# Heater.net
KiCad netlist of a schematic drawn in Altium Designer
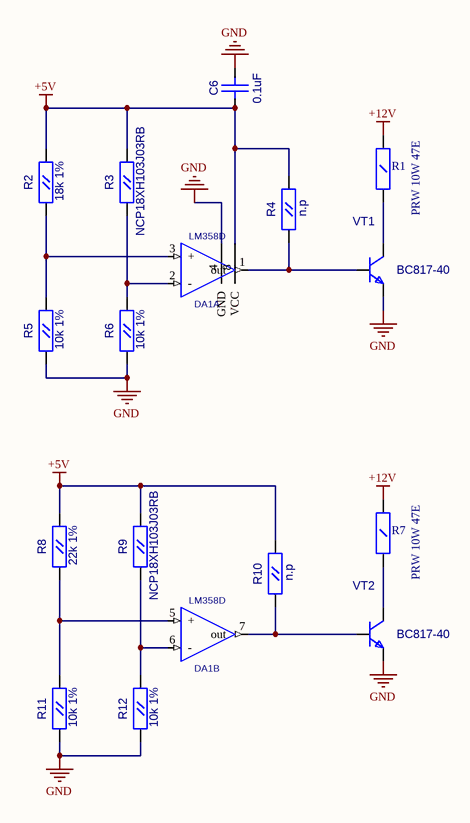
[diagram p0: Heater.SchDoc]

(export (version "E")
  (design (tool "Eeschema 10.0.6"))
  (components
    (comp (ref "C6")
      (value "0.1uF")
      (footprint "CC0603")
      (description "CC0603")
      (libsource (lib "gprs_modem_2") (part "CC0603"))
    )
    (comp (ref "DA1") (value "LM358D") (footprint "SO-8") (libsource (lib "Schetchik") (part "LM358D")))
    (comp (ref "R1")
      (value "PRW 10W 47E")
      (footprint "R_5W_Cement")
      (libsource (lib "gprs_modem_2") (part "R_10W"))
    )
    (comp (ref "R2")
      (value "18k 1%")
      (footprint "RC0603")
      (description "RC0603")
      (libsource (lib "gprs_modem_2") (part "RC0603"))
    )
    (comp (ref "R3")
      (value "NCP18XH103J03RB")
      (footprint "RC0603")
      (description "RC0603")
      (libsource (lib "gprs_modem_2") (part "RC0603"))
    )
    (comp (ref "R4")
      (value "n.p")
      (footprint "RC0603")
      (description "RC0603")
      (libsource (lib "gprs_modem_2") (part "RC0603"))
    )
    (comp (ref "R5")
      (value "10k 1%")
      (footprint "RC0603")
      (description "RC0603")
      (libsource (lib "gprs_modem_2") (part "RC0603"))
    )
    (comp (ref "R6")
      (value "10k 1%")
      (footprint "RC0603")
      (description "RC0603")
      (libsource (lib "gprs_modem_2") (part "RC0603"))
    )
    (comp (ref "R7")
      (value "PRW 10W 47E")
      (footprint "R_5W_Cement")
      (libsource (lib "gprs_modem_2") (part "R_10W"))
    )
    (comp (ref "R8")
      (value "22k 1%")
      (footprint "RC0603")
      (description "RC0603")
      (libsource (lib "gprs_modem_2") (part "RC0603"))
    )
    (comp (ref "R9")
      (value "NCP18XH103J03RB")
      (footprint "RC0603")
      (description "RC0603")
      (libsource (lib "gprs_modem_2") (part "RC0603"))
    )
    (comp (ref "R10")
      (value "n.p")
      (footprint "RC0603")
      (description "RC0603")
      (libsource (lib "gprs_modem_2") (part "RC0603"))
    )
    (comp (ref "R11")
      (value "10k 1%")
      (footprint "RC0603")
      (description "RC0603")
      (libsource (lib "gprs_modem_2") (part "RC0603"))
    )
    (comp (ref "R12")
      (value "10k 1%")
      (footprint "RC0603")
      (description "RC0603")
      (libsource (lib "gprs_modem_2") (part "RC0603"))
    )
    (comp (ref "VT1")
      (value "BC817-40")
      (footprint "SOT-23(123)")
      (description "NPN 500ma transistor")
      (libsource (lib "gprs_modem_2") (part "BC846BLT1"))
    )
    (comp (ref "VT2")
      (value "BC817-40")
      (footprint "SOT-23(123)")
      (description "NPN 500ma transistor")
      (libsource (lib "gprs_modem_2") (part "BC846BLT1"))
    )
  )
  (nets
    (net (code "1") (name "+5V") (class "Default")
      (node (ref "C6") (pin "1") (pinfunction "A_1") (pintype "passive"))
      (node (ref "DA1") (pin "8") (pinfunction "VCC_8") (pintype "power_in"))
      (node (ref "R10") (pin "2") (pinfunction "B_2") (pintype "passive"))
      (node (ref "R2") (pin "2") (pinfunction "B_2") (pintype "passive"))
      (node (ref "R3") (pin "2") (pinfunction "B_2") (pintype "passive"))
      (node (ref "R4") (pin "2") (pinfunction "B_2") (pintype "passive"))
      (node (ref "R8") (pin "2") (pinfunction "B_2") (pintype "passive"))
      (node (ref "R9") (pin "2") (pinfunction "B_2") (pintype "passive"))
    )
    (net (code "2") (name "+12V") (class "Default")
      (node (ref "R1") (pin "2") (pinfunction "B_2") (pintype "passive"))
      (node (ref "R7") (pin "2") (pinfunction "B_2") (pintype "passive"))
    )
    (net (code "3") (name "GND") (class "Default")
      (node (ref "C6") (pin "2") (pinfunction "B_2") (pintype "passive"))
      (node (ref "DA1") (pin "4") (pinfunction "GND_4") (pintype "power_in"))
      (node (ref "R11") (pin "1") (pinfunction "A_1") (pintype "passive"))
      (node (ref "R12") (pin "1") (pinfunction "A_1") (pintype "passive"))
      (node (ref "R5") (pin "1") (pinfunction "A_1") (pintype "passive"))
      (node (ref "R6") (pin "1") (pinfunction "A_1") (pintype "passive"))
      (node (ref "VT1") (pin "2") (pinfunction "E_2") (pintype "passive"))
      (node (ref "VT2") (pin "2") (pinfunction "E_2") (pintype "passive"))
    )
    (net (code "4") (name "Net-(DA1A-+)") (class "Default")
      (node (ref "DA1") (pin "3") (pinfunction "+_3") (pintype "input"))
      (node (ref "R2") (pin "1") (pinfunction "A_1") (pintype "passive"))
      (node (ref "R5") (pin "2") (pinfunction "B_2") (pintype "passive"))
    )
    (net (code "5") (name "Net-(DA1A--)") (class "Default")
      (node (ref "DA1") (pin "2") (pinfunction "-_2") (pintype "input"))
      (node (ref "R3") (pin "1") (pinfunction "A_1") (pintype "passive"))
      (node (ref "R6") (pin "2") (pinfunction "B_2") (pintype "passive"))
    )
    (net (code "6") (name "Net-(DA1A-out)") (class "Default")
      (node (ref "DA1") (pin "1") (pinfunction "out_1") (pintype "output"))
      (node (ref "R4") (pin "1") (pinfunction "A_1") (pintype "passive"))
      (node (ref "VT1") (pin "1") (pinfunction "B_1") (pintype "passive"))
    )
    (net (code "7") (name "Net-(DA1B-+)") (class "Default")
      (node (ref "DA1") (pin "5") (pinfunction "+_5") (pintype "input"))
      (node (ref "R11") (pin "2") (pinfunction "B_2") (pintype "passive"))
      (node (ref "R8") (pin "1") (pinfunction "A_1") (pintype "passive"))
    )
    (net (code "8") (name "Net-(DA1B--)") (class "Default")
      (node (ref "DA1") (pin "6") (pinfunction "-_6") (pintype "input"))
      (node (ref "R12") (pin "2") (pinfunction "B_2") (pintype "passive"))
      (node (ref "R9") (pin "1") (pinfunction "A_1") (pintype "passive"))
    )
    (net (code "9") (name "Net-(DA1B-out)") (class "Default")
      (node (ref "DA1") (pin "7") (pinfunction "out_7") (pintype "output"))
      (node (ref "R10") (pin "1") (pinfunction "A_1") (pintype "passive"))
      (node (ref "VT2") (pin "1") (pinfunction "B_1") (pintype "passive"))
    )
    (net (code "10") (name "Net-(R1-A)") (class "Default")
      (node (ref "R1") (pin "1") (pinfunction "A_1") (pintype "passive"))
      (node (ref "VT1") (pin "3") (pinfunction "C_3") (pintype "passive"))
    )
    (net (code "11") (name "Net-(R7-A)") (class "Default")
      (node (ref "R7") (pin "1") (pinfunction "A_1") (pintype "passive"))
      (node (ref "VT2") (pin "3") (pinfunction "C_3") (pintype "passive"))
    )
  )
)
